# placa_painel.net
KiCad netlist of a schematic drawn in EAGLE
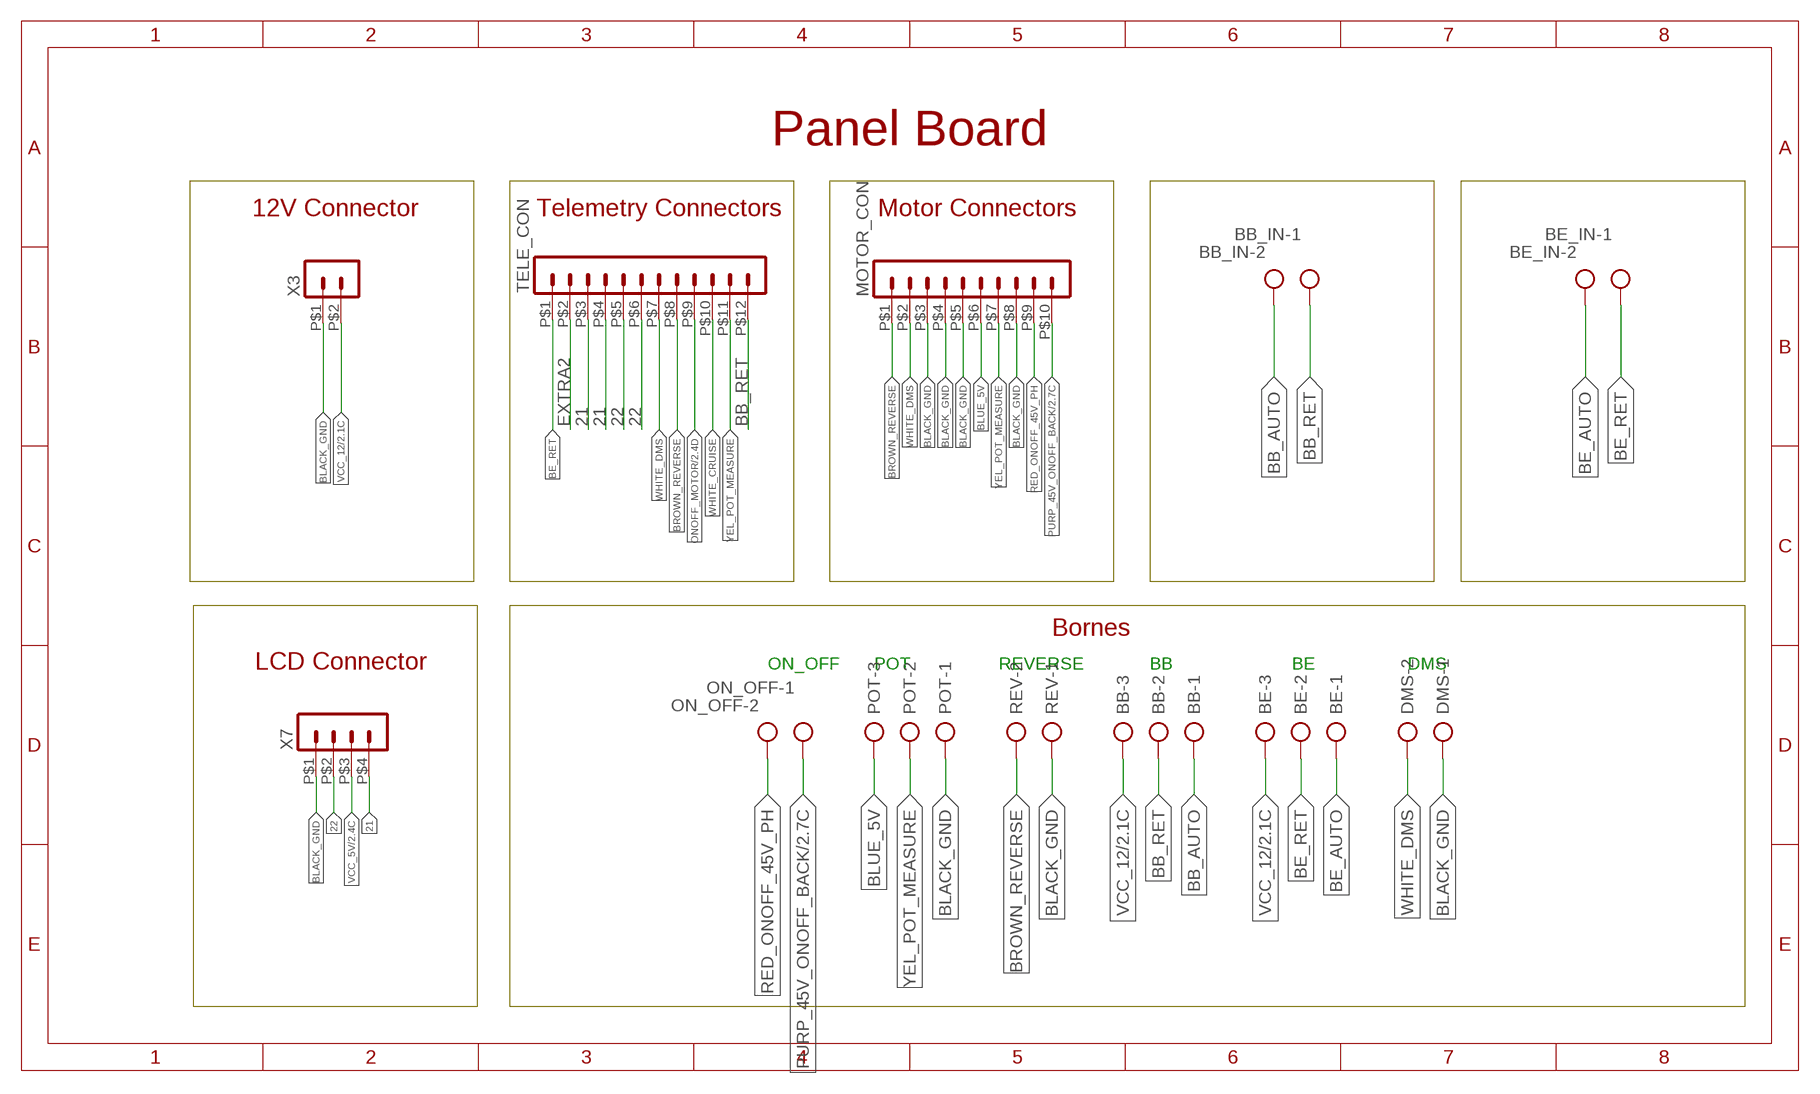
[diagram p0: schematic, sheet 1]
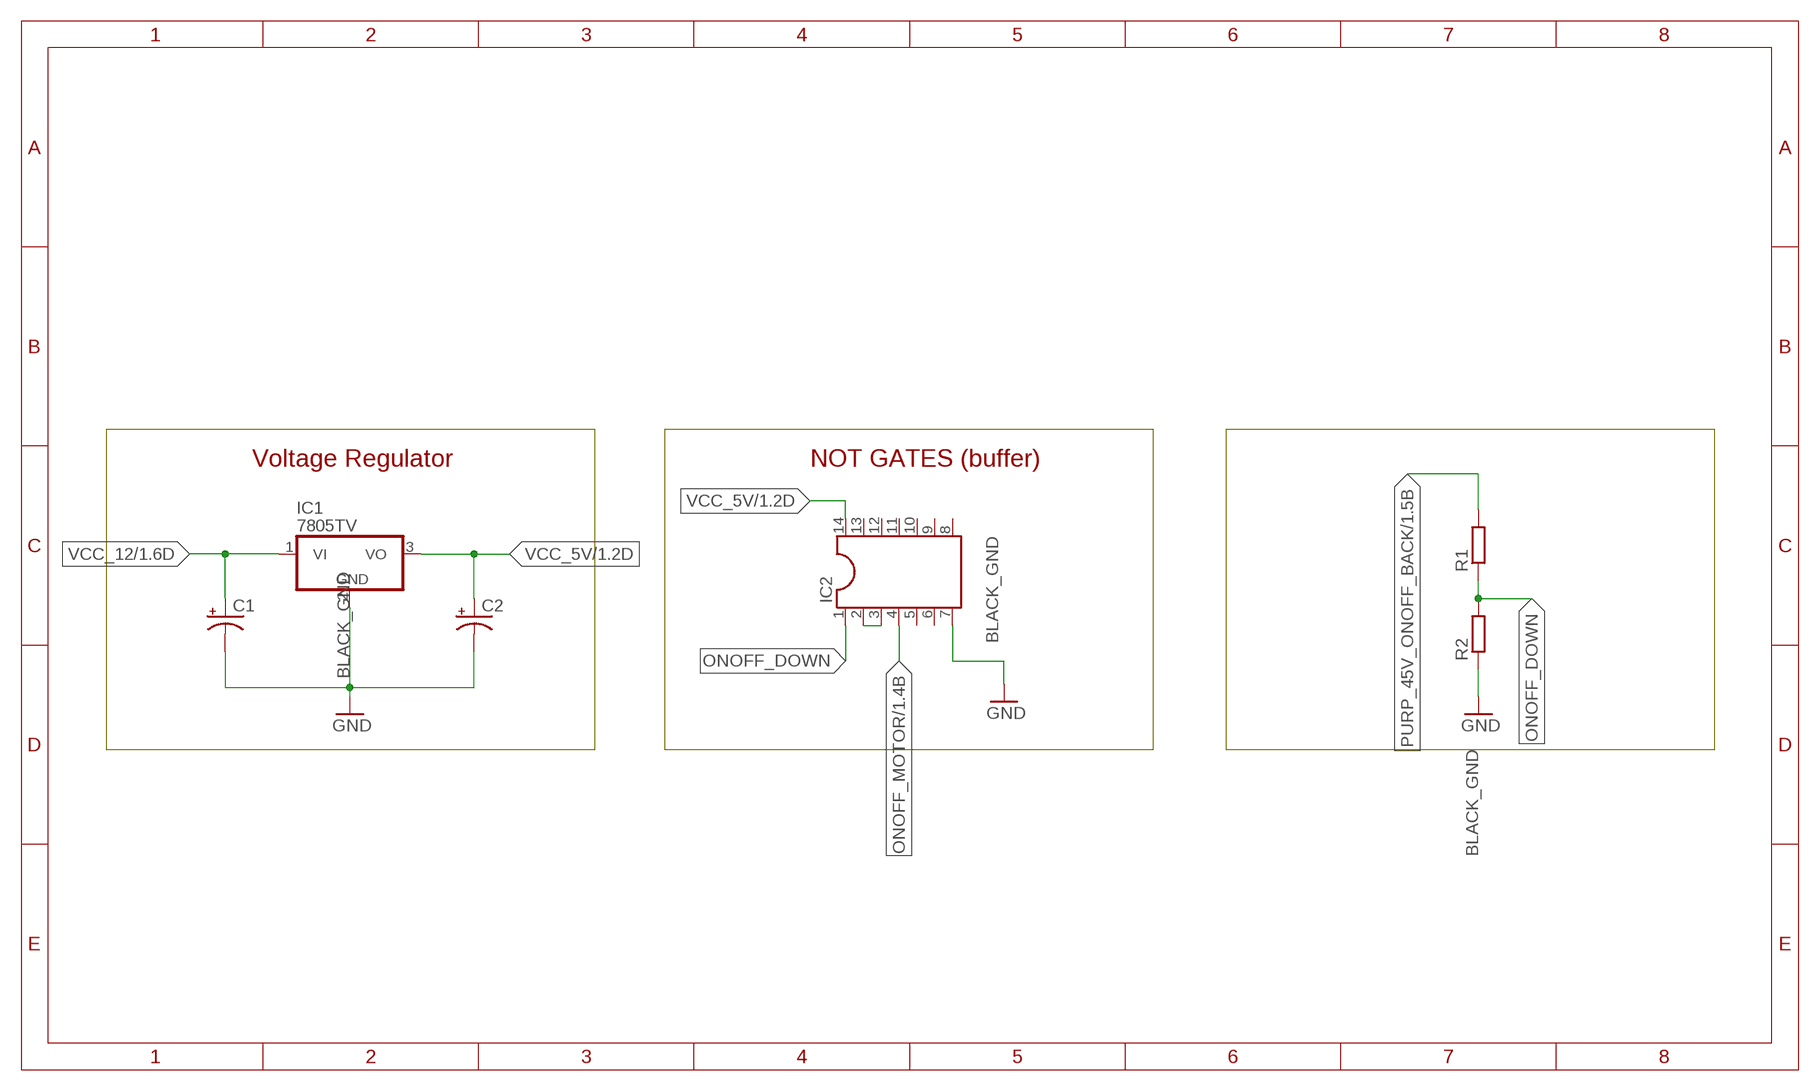
[diagram p1: schematic, sheet 2]

(export (version "E")
  (design (tool "Eeschema 10.0.6"))
  (components
    (comp (ref "C1")
      (value "CPOL-USE5-5")
      (footprint "eagle-import:E5-5")
      (libsource (lib "eagle-import") (part "CPOL-USE5-5"))
    )
    (comp (ref "C2")
      (value "CPOL-USE5-5")
      (footprint "eagle-import:E5-5")
      (libsource (lib "eagle-import") (part "CPOL-USE5-5"))
    )
    (comp (ref "IC1")
      (value "7805TV")
      (footprint "eagle-import:TO220V")
      (libsource (lib "eagle-import") (part "78TV05"))
    )
    (comp (ref "IC2")
      (value "DIL14")
      (footprint "eagle-import:DIL14")
      (libsource (lib "eagle-import") (part "DIL14"))
    )
    (comp (ref "R1")
      (value "R-EU_0204/7")
      (footprint "eagle-import:0204_7")
      (libsource (lib "eagle-import") (part "R-EU_0204/7"))
    )
    (comp (ref "R2")
      (value "R-EU_0204/7")
      (footprint "eagle-import:0204_7")
      (libsource (lib "eagle-import") (part "R-EU_0204/7"))
    )
    (comp (ref "BB")
      (value "AK500/3")
      (footprint "eagle-import:AK500_3")
      (libsource (lib "eagle-import") (part "AK500/3"))
    )
    (comp (ref "BB_IN")
      (value "AK500/2")
      (footprint "eagle-import:AK500_2")
      (libsource (lib "eagle-import") (part "AK500/2"))
    )
    (comp (ref "BE")
      (value "AK500/3")
      (footprint "eagle-import:AK500_3")
      (libsource (lib "eagle-import") (part "AK500/3"))
    )
    (comp (ref "BE_IN")
      (value "AK500/2")
      (footprint "eagle-import:AK500_2")
      (libsource (lib "eagle-import") (part "AK500/2"))
    )
    (comp (ref "DMS")
      (value "AK500/2")
      (footprint "eagle-import:AK500_2")
      (libsource (lib "eagle-import") (part "AK500/2"))
    )
    (comp (ref "MOTOR_CON")
      (value "HEADER_POS10_43045-1012")
      (footprint "eagle-import:43045-1012")
      (libsource (lib "eagle-import") (part "HEADER_POS10_?43045-1012"))
    )
    (comp (ref "ON_OFF")
      (value "AK500/2")
      (footprint "eagle-import:AK500_2")
      (libsource (lib "eagle-import") (part "AK500/2"))
    )
    (comp (ref "POT")
      (value "AK500/3")
      (footprint "eagle-import:AK500_3")
      (libsource (lib "eagle-import") (part "AK500/3"))
    )
    (comp (ref "REV")
      (value "AK500/2")
      (footprint "eagle-import:AK500_2")
      (libsource (lib "eagle-import") (part "AK500/2"))
    )
    (comp (ref "TELE_CON")
      (value "HEADER_POS12_43045-1212")
      (footprint "eagle-import:43045-1212")
      (libsource (lib "eagle-import") (part "HEADER_POS12_?43045-1212"))
    )
    (comp (ref "X3")
      (value "HEADER_POS2_43045-0212")
      (footprint "eagle-import:43045-0212")
      (libsource (lib "eagle-import") (part "HEADER_POS2_?43045-0212"))
    )
    (comp (ref "X7")
      (value "HEADER_POS4_43045-0412")
      (footprint "eagle-import:43045-0412")
      (libsource (lib "eagle-import") (part "HEADER_POS4_?43045-0412"))
    )
  )
  (nets
    (net (code "1") (name "21") (class "Default")
      (node (ref "TELE_CON") (pin "P$3") (pinfunction "3_P$3") (pintype "passive"))
      (node (ref "TELE_CON") (pin "P$4") (pinfunction "4_P$4") (pintype "passive"))
      (node (ref "X7") (pin "P$4") (pinfunction "4_P$4") (pintype "passive"))
    )
    (net (code "2") (name "22") (class "Default")
      (node (ref "TELE_CON") (pin "P$5") (pinfunction "5_P$5") (pintype "passive"))
      (node (ref "TELE_CON") (pin "P$6") (pinfunction "6_P$6") (pintype "passive"))
      (node (ref "X7") (pin "P$2") (pinfunction "2_P$2") (pintype "passive"))
    )
    (net (code "3") (name "BB_AUTO") (class "Default")
      (node (ref "BB") (pin "1") (pinfunction "KL_1") (pintype "passive"))
      (node (ref "BB_IN") (pin "2") (pinfunction "KL_2") (pintype "passive"))
    )
    (net (code "4") (name "BB_RET") (class "Default")
      (node (ref "BB") (pin "2") (pinfunction "KL_2") (pintype "passive"))
      (node (ref "BB_IN") (pin "1") (pinfunction "KL_1") (pintype "passive"))
      (node (ref "TELE_CON") (pin "P$12") (pinfunction "12_P$12") (pintype "passive"))
    )
    (net (code "5") (name "BE_AUTO") (class "Default")
      (node (ref "BE") (pin "1") (pinfunction "KL_1") (pintype "passive"))
      (node (ref "BE_IN") (pin "2") (pinfunction "KL_2") (pintype "passive"))
    )
    (net (code "6") (name "BE_RET") (class "Default")
      (node (ref "BE") (pin "2") (pinfunction "KL_2") (pintype "passive"))
      (node (ref "BE_IN") (pin "1") (pinfunction "KL_1") (pintype "passive"))
      (node (ref "TELE_CON") (pin "P$1") (pinfunction "1_P$1") (pintype "passive"))
    )
    (net (code "7") (name "BLACK_GND") (class "Default")
      (node (ref "C1") (pin "-") (pinfunction "-_-") (pintype "passive"))
      (node (ref "C2") (pin "-") (pinfunction "-_-") (pintype "passive"))
      (node (ref "DMS") (pin "1") (pinfunction "KL_1") (pintype "passive"))
      (node (ref "IC1") (pin "2") (pinfunction "GND_2") (pintype "passive"))
      (node (ref "IC2") (pin "7") (pinfunction "7_7") (pintype "passive"))
      (node (ref "MOTOR_CON") (pin "P$3") (pinfunction "3_P$3") (pintype "passive"))
      (node (ref "MOTOR_CON") (pin "P$4") (pinfunction "4_P$4") (pintype "passive"))
      (node (ref "MOTOR_CON") (pin "P$5") (pinfunction "5_P$5") (pintype "passive"))
      (node (ref "MOTOR_CON") (pin "P$8") (pinfunction "8_P$8") (pintype "passive"))
      (node (ref "POT") (pin "1") (pinfunction "KL_1") (pintype "passive"))
      (node (ref "R2") (pin "1") (pinfunction "1_1") (pintype "passive"))
      (node (ref "REV") (pin "1") (pinfunction "KL_1") (pintype "passive"))
      (node (ref "X3") (pin "P$1") (pinfunction "1_P$1") (pintype "passive"))
      (node (ref "X7") (pin "P$1") (pinfunction "1_P$1") (pintype "passive"))
    )
    (net (code "8") (name "BLUE_5V") (class "Default")
      (node (ref "MOTOR_CON") (pin "P$6") (pinfunction "6_P$6") (pintype "passive"))
      (node (ref "POT") (pin "3") (pinfunction "KL_3") (pintype "passive"))
    )
    (net (code "9") (name "BROWN_REVERSE") (class "Default")
      (node (ref "MOTOR_CON") (pin "P$1") (pinfunction "1_P$1") (pintype "passive"))
      (node (ref "REV") (pin "2") (pinfunction "KL_2") (pintype "passive"))
      (node (ref "TELE_CON") (pin "P$8") (pinfunction "8_P$8") (pintype "passive"))
    )
    (net (code "10") (name "EXTRA2") (class "Default")
      (node (ref "TELE_CON") (pin "P$2") (pinfunction "2_P$2") (pintype "passive"))
    )
    (net (code "11") (name "Net-(IC2-Pad2)") (class "Default")
      (node (ref "IC2") (pin "2") (pinfunction "2_2") (pintype "passive"))
      (node (ref "IC2") (pin "3") (pinfunction "3_3") (pintype "passive"))
    )
    (net (code "12") (name "ONOFF_DOWN") (class "Default")
      (node (ref "IC2") (pin "1") (pinfunction "1_1") (pintype "passive"))
      (node (ref "R1") (pin "1") (pinfunction "1_1") (pintype "passive"))
      (node (ref "R2") (pin "2") (pinfunction "2_2") (pintype "passive"))
    )
    (net (code "13") (name "ONOFF_MOTOR") (class "Default")
      (node (ref "IC2") (pin "4") (pinfunction "4_4") (pintype "passive"))
      (node (ref "TELE_CON") (pin "P$9") (pinfunction "9_P$9") (pintype "passive"))
    )
    (net (code "14") (name "PURP_45V_ONOFF_BACK") (class "Default")
      (node (ref "MOTOR_CON") (pin "P$10") (pinfunction "10_P$10") (pintype "passive"))
      (node (ref "ON_OFF") (pin "1") (pinfunction "KL_1") (pintype "passive"))
      (node (ref "R1") (pin "2") (pinfunction "2_2") (pintype "passive"))
    )
    (net (code "15") (name "RED_ONOFF_45V_PH") (class "Default")
      (node (ref "MOTOR_CON") (pin "P$9") (pinfunction "9_P$9") (pintype "passive"))
      (node (ref "ON_OFF") (pin "2") (pinfunction "KL_2") (pintype "passive"))
    )
    (net (code "16") (name "VCC_5V") (class "Default")
      (node (ref "C2") (pin "+") (pinfunction "+_+") (pintype "passive"))
      (node (ref "IC1") (pin "3") (pinfunction "VO_3") (pintype "passive"))
      (node (ref "IC2") (pin "14") (pinfunction "14_14") (pintype "passive"))
      (node (ref "X7") (pin "P$3") (pinfunction "3_P$3") (pintype "passive"))
    )
    (net (code "17") (name "VCC_12") (class "Default")
      (node (ref "BB") (pin "3") (pinfunction "KL_3") (pintype "passive"))
      (node (ref "BE") (pin "3") (pinfunction "KL_3") (pintype "passive"))
      (node (ref "C1") (pin "+") (pinfunction "+_+") (pintype "passive"))
      (node (ref "IC1") (pin "1") (pinfunction "VI_1") (pintype "input"))
      (node (ref "X3") (pin "P$2") (pinfunction "2_P$2") (pintype "passive"))
    )
    (net (code "18") (name "WHITE_CRUISE") (class "Default")
      (node (ref "TELE_CON") (pin "P$10") (pinfunction "10_P$10") (pintype "passive"))
    )
    (net (code "19") (name "WHITE_DMS") (class "Default")
      (node (ref "DMS") (pin "2") (pinfunction "KL_2") (pintype "passive"))
      (node (ref "MOTOR_CON") (pin "P$2") (pinfunction "2_P$2") (pintype "passive"))
      (node (ref "TELE_CON") (pin "P$7") (pinfunction "7_P$7") (pintype "passive"))
    )
    (net (code "20") (name "YEL_POT_MEASURE") (class "Default")
      (node (ref "MOTOR_CON") (pin "P$7") (pinfunction "7_P$7") (pintype "passive"))
      (node (ref "POT") (pin "2") (pinfunction "KL_2") (pintype "passive"))
      (node (ref "TELE_CON") (pin "P$11") (pinfunction "11_P$11") (pintype "passive"))
    )
    (net (code "21") (name "unconnected-(IC2-Pad5)") (class "Default")
      (node (ref "IC2") (pin "5") (pinfunction "5_5") (pintype "passive"))
    )
    (net (code "22") (name "unconnected-(IC2-Pad6)") (class "Default")
      (node (ref "IC2") (pin "6") (pinfunction "6_6") (pintype "passive"))
    )
    (net (code "23") (name "unconnected-(IC2-Pad8)") (class "Default")
      (node (ref "IC2") (pin "8") (pinfunction "8_8") (pintype "passive"))
    )
    (net (code "24") (name "unconnected-(IC2-Pad9)") (class "Default")
      (node (ref "IC2") (pin "9") (pinfunction "9_9") (pintype "passive"))
    )
    (net (code "25") (name "unconnected-(IC2-Pad10)") (class "Default")
      (node (ref "IC2") (pin "10") (pinfunction "10_10") (pintype "passive"))
    )
    (net (code "26") (name "unconnected-(IC2-Pad11)") (class "Default")
      (node (ref "IC2") (pin "11") (pinfunction "11_11") (pintype "passive"))
    )
    (net (code "27") (name "unconnected-(IC2-Pad12)") (class "Default")
      (node (ref "IC2") (pin "12") (pinfunction "12_12") (pintype "passive"))
    )
    (net (code "28") (name "unconnected-(IC2-Pad13)") (class "Default")
      (node (ref "IC2") (pin "13") (pinfunction "13_13") (pintype "passive"))
    )
  )
)
